# Filtr1.net
KiCad netlist of a schematic drawn in Altium Designer
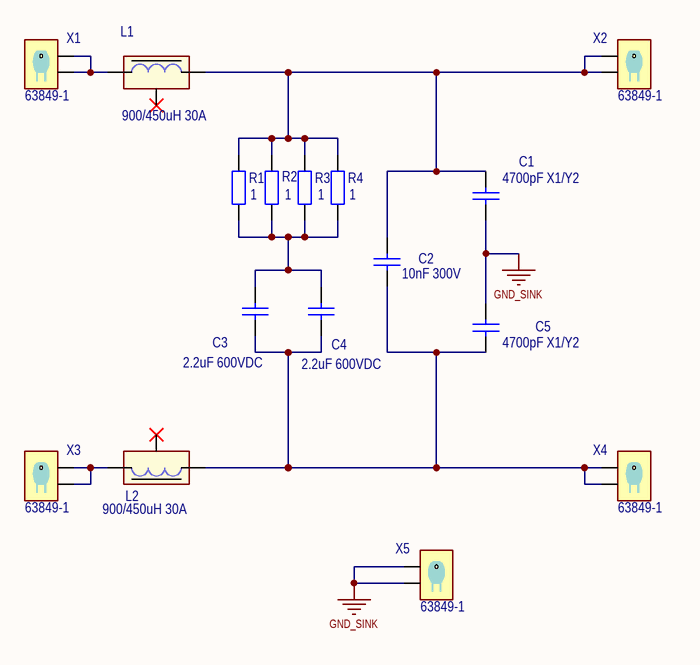
[diagram p0: Filtr1.SchDoc]

(export (version "E")
  (design (tool "Eeschema 10.0.6"))
  (components
    (comp (ref "C1")
      (value "4700pF X1/Y2")
      (footprint "mainLib:SMD_C_2220")
      (description "SMD C2220 MURATA 250Vac 10% X7R X1Y2")
      (fields (field (name "PARTNUMBER") "DE2E3KY472MA3") (field (name "MANUFACTURER") "MURATA"))
      (libsource (lib "mainRCLib") (part "C X1Y2 4700pF SMD 2220 250Vac 10%"))
    )
    (comp (ref "C2")
      (value "10nF 300V")
      (footprint "mainLib:C Y2 D13 7.5b")
      (description "Ceramic D=14 LS=7.5 300VAC X1Y2")
      (fields (field (name "PARTNUMBER") "DE2F3KY103MA3") (field (name "MANUFACTURER") "Murata"))
      (libsource (lib "mainRCLib") (part "C X1Y2 10nF D13 LS7.5"))
    )
    (comp (ref "C3")
      (value "2.2uF 600VDC")
      (footprint "mainLib:MKP_W20_H39.5_L41.5_LS37.5")
      (description "Polypropelene W20 H39.5 L41.5 LS37.5 600VDC 10%")
      (fields (field (name "PARTNUMBER") "MKP1J042207G00K") (field (name "MANUFACTURER") "Wima"))
      (libsource (lib "mainRCLib") (part "MKP1 2.2uF 10% 600VDC"))
    )
    (comp (ref "C4")
      (value "2.2uF 600VDC")
      (footprint "mainLib:MKP_W20_H39.5_L41.5_LS37.5")
      (description "Polypropelene W20 H39.5 L41.5 LS37.5 600VDC 10%")
      (fields (field (name "PARTNUMBER") "MKP1J042207G00K") (field (name "MANUFACTURER") "Wima"))
      (libsource (lib "mainRCLib") (part "MKP1 2.2uF 10% 600VDC"))
    )
    (comp (ref "C5")
      (value "4700pF X1/Y2")
      (footprint "mainLib:SMD_C_2220")
      (description "SMD C2220 MURATA 250Vac 10% X7R X1Y2")
      (fields (field (name "PARTNUMBER") "DE2E3KY472MA3") (field (name "MANUFACTURER") "MURATA"))
      (libsource (lib "mainRCLib") (part "C X1Y2 4700pF SMD 2220 250Vac 10%"))
    )
    (comp (ref "L1")
      (value "900/450uH 30A")
      (footprint "mainLib:Dross (900/450 uH) R100230.041.000")
      (description "1000/250uH 30A  (Core CK40090 X2)")
      (fields (field (name "MANUFACTURER") "OLTEST") (field (name "PARTNUMBER") "R100.230.041.000"))
      (libsource (lib "mainLib") (part "Dross 900/450uH 30A R100.230.041.000"))
    )
    (comp (ref "L2")
      (value "900/450uH 30A")
      (footprint "mainLib:Dross (900/450 uH) R100230.041.000")
      (description "1000/250uH 30A  (Core CK40090 X2)")
      (fields (field (name "MANUFACTURER") "OLTEST") (field (name "PARTNUMBER") "R100.230.041.000"))
      (libsource (lib "") (part "Dross 900/450uH 30A R100.230.041.000_1"))
    )
    (comp (ref "R1")
      (value "1")
      (footprint "mainLib:PRW 5W vertical")
      (description "Выводной PRW 5W 1R +-5%")
      (fields (field (name "PARTNUMBER") "PRW05WJW10J") (field (name "MANUFACTURER") "RoyalOhm"))
      (libsource (lib "") (part "PRW 1 5W +-5%_1_1"))
    )
    (comp (ref "R2")
      (value "1")
      (footprint "mainLib:PRW 5W vertical")
      (description "Выводной PRW 5W 1R +-5%")
      (fields (field (name "PARTNUMBER") "PRW05WJW10J") (field (name "MANUFACTURER") "RoyalOhm"))
      (libsource (lib "") (part "PRW 1 5W +-5%_1_1"))
    )
    (comp (ref "R3")
      (value "1")
      (footprint "mainLib:PRW 5W vertical")
      (description "Выводной PRW 5W 1R +-5%")
      (fields (field (name "PARTNUMBER") "PRW05WJW10J") (field (name "MANUFACTURER") "RoyalOhm"))
      (libsource (lib "mainRCLib") (part "PRW 1 5W +-5%_1"))
    )
    (comp (ref "R4")
      (value "1")
      (footprint "mainLib:PRW 5W vertical")
      (description "Выводной PRW 5W 1R +-5%")
      (fields (field (name "PARTNUMBER") "PRW05WJW10J") (field (name "MANUFACTURER") "RoyalOhm"))
      (libsource (lib "mainRCLib") (part "PRW 1 5W +-5%_1"))
    )
    (comp (ref "X1")
      (value "63849-1")
      (footprint "mainLib:63849-1+insulator(154719-1)")
      (description "PCB, 6.3х0.8, hole")
      (fields (field (name "MANUFACTURER") "TE Connectivity"))
      (libsource (lib "mainLib") (part "63849-1"))
    )
    (comp (ref "X2")
      (value "63849-1")
      (footprint "mainLib:63849-1+insulator(154719-1)")
      (description "PCB, 6.3х0.8, hole")
      (fields (field (name "MANUFACTURER") "TE Connectivity"))
      (libsource (lib "") (part "63849-1_1"))
    )
    (comp (ref "X3")
      (value "63849-1")
      (footprint "mainLib:63849-1+insulator(154719-1)")
      (description "PCB, 6.3х0.8, hole")
      (fields (field (name "MANUFACTURER") "TE Connectivity"))
      (libsource (lib "mainLib") (part "63849-1"))
    )
    (comp (ref "X4")
      (value "63849-1")
      (footprint "mainLib:63849-1+insulator(154719-1)")
      (description "PCB, 6.3х0.8, hole")
      (fields (field (name "MANUFACTURER") "TE Connectivity"))
      (libsource (lib "") (part "63849-1_1"))
    )
    (comp (ref "X5")
      (value "63849-1")
      (footprint "mainLib:63849-1+insulator(154719-1)")
      (description "PCB, 6.3х0.8, hole")
      (fields (field (name "MANUFACTURER") "TE Connectivity"))
      (libsource (lib "") (part "63849-1_1"))
    )
  )
  (nets
    (net (code "1") (name "GND_SINK") (class "Default")
      (node (ref "C1") (pin "1") (pinfunction "1_1") (pintype "passive"))
      (node (ref "C5") (pin "2") (pinfunction "2_2") (pintype "passive"))
      (node (ref "X5") (pin "1") (pinfunction "1_1") (pintype "passive"))
      (node (ref "X5") (pin "2") (pinfunction "2_2") (pintype "passive"))
    )
    (net (code "2") (name "Net-(C1-Pad2)") (class "Default")
      (node (ref "C1") (pin "2") (pinfunction "2_2") (pintype "passive"))
      (node (ref "C2") (pin "2") (pinfunction "2_2") (pintype "passive"))
      (node (ref "L1") (pin "2") (pinfunction "2_2") (pintype "passive"))
      (node (ref "R1") (pin "2") (pinfunction "2_2") (pintype "passive"))
      (node (ref "R2") (pin "2") (pinfunction "2_2") (pintype "passive"))
      (node (ref "R3") (pin "1") (pinfunction "1_1") (pintype "passive"))
      (node (ref "R4") (pin "1") (pinfunction "1_1") (pintype "passive"))
      (node (ref "X2") (pin "1") (pinfunction "1_1") (pintype "passive"))
      (node (ref "X2") (pin "2") (pinfunction "2_2") (pintype "passive"))
    )
    (net (code "3") (name "Net-(C2-Pad1)") (class "Default")
      (node (ref "C2") (pin "1") (pinfunction "1_1") (pintype "passive"))
      (node (ref "C3") (pin "2") (pinfunction "2_2") (pintype "passive"))
      (node (ref "C4") (pin "1") (pinfunction "1_1") (pintype "passive"))
      (node (ref "C5") (pin "1") (pinfunction "1_1") (pintype "passive"))
      (node (ref "L2") (pin "2") (pinfunction "2_2") (pintype "passive"))
      (node (ref "X4") (pin "1") (pinfunction "1_1") (pintype "passive"))
      (node (ref "X4") (pin "2") (pinfunction "2_2") (pintype "passive"))
    )
    (net (code "4") (name "Net-(C3-Pad1)") (class "Default")
      (node (ref "C3") (pin "1") (pinfunction "1_1") (pintype "passive"))
      (node (ref "C4") (pin "2") (pinfunction "2_2") (pintype "passive"))
      (node (ref "R1") (pin "1") (pinfunction "1_1") (pintype "passive"))
      (node (ref "R2") (pin "1") (pinfunction "1_1") (pintype "passive"))
      (node (ref "R3") (pin "2") (pinfunction "2_2") (pintype "passive"))
      (node (ref "R4") (pin "2") (pinfunction "2_2") (pintype "passive"))
    )
    (net (code "5") (name "Net-(L1-Pad1)") (class "Default")
      (node (ref "L1") (pin "1") (pinfunction "1_1") (pintype "passive"))
      (node (ref "X1") (pin "1") (pinfunction "1_1") (pintype "passive"))
      (node (ref "X1") (pin "2") (pinfunction "2_2") (pintype "passive"))
    )
    (net (code "6") (name "Net-(L2-Pad1)") (class "Default")
      (node (ref "L2") (pin "1") (pinfunction "1_1") (pintype "passive"))
      (node (ref "X3") (pin "1") (pinfunction "1_1") (pintype "passive"))
      (node (ref "X3") (pin "2") (pinfunction "2_2") (pintype "passive"))
    )
    (net (code "7") (name "unconnected-(L1-Pad3)") (class "Default")
      (node (ref "L1") (pin "3") (pinfunction "3_3") (pintype "passive+no_connect"))
    )
    (net (code "8") (name "unconnected-(L2-Pad3)") (class "Default")
      (node (ref "L2") (pin "3") (pinfunction "3_3") (pintype "passive+no_connect"))
    )
  )
)
